# PCB.net
KiCad netlist of a schematic drawn in Altium Designer
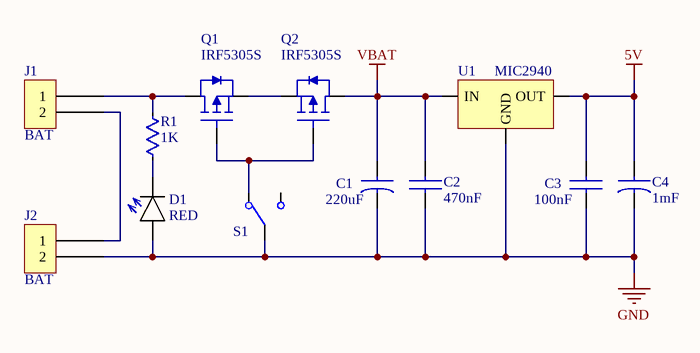
[diagram p0: PCB.SchDoc]

(export (version "E")
  (design (tool "Eeschema 10.0.6"))
  (components
    (comp (ref "C1")
      (value "220uF")
      (footprint "CAP-ELEC-5x11x2mm")
      (fields (field (name "Comment") "CAP-ELEC"))
      (libsource (lib "AltiumLibrary") (part "CAP-ELEC"))
    )
    (comp (ref "C2")
      (value "470nF")
      (footprint "C1206")
      (fields (field (name "Comment") "CAP-CER"))
      (libsource (lib "AltiumLibrary") (part "CAP-CER"))
    )
    (comp (ref "C3")
      (value "100nF")
      (footprint "C1206")
      (fields (field (name "Comment") "CAP-CER"))
      (libsource (lib "AltiumLibrary") (part "CAP-CER"))
    )
    (comp (ref "C4")
      (value "1mF")
      (footprint "CAP-ELEC-5x11x2mm")
      (fields (field (name "Comment") "CAP-ELEC"))
      (libsource (lib "AltiumLibrary") (part "CAP-ELEC"))
    )
    (comp (ref "D1") (value "RED") (footprint "LED-3MM-RED") (libsource (lib "AltiumLibrary") (part "LED")))
    (comp (ref "J1")
      (value "BAT")
      (footprint "HEADER 1x2")
      (libsource (lib "AltiumLibrary") (part "Header 1x2"))
    )
    (comp (ref "J2")
      (value "BAT")
      (footprint "HEADER 1x2")
      (libsource (lib "AltiumLibrary") (part "Header 1x2"))
    )
    (comp (ref "Q1")
      (value "IRF5305S")
      (footprint "TO-263")
      (libsource (lib "AltiumLibrary") (part "P-MOSFET"))
    )
    (comp (ref "Q2")
      (value "IRF5305S")
      (footprint "TO-263")
      (libsource (lib "AltiumLibrary") (part "P-MOSFET"))
    )
    (comp (ref "R1")
      (value "1K")
      (footprint "R1206")
      (fields (field (name "Comment") "RES"))
      (libsource (lib "AltiumLibrary") (part "RES"))
    )
    (comp (ref "S1")
      (value "SLIDE-SWITCH")
      (footprint "SWITCH")
      (libsource (lib "AltiumLibrary") (part "SLIDE-SWITCH"))
    )
    (comp (ref "U1") (value "MIC2940") (footprint "TO-263") (libsource (lib "AltiumLibrary") (part "LM2940")))
  )
  (nets
    (net (code "1") (name "5V") (class "Default")
      (node (ref "C3") (pin "2") (pintype "passive"))
      (node (ref "C4") (pin "1") (pintype "passive"))
      (node (ref "U1") (pin "3") (pinfunction "OUT_3") (pintype "power_in"))
    )
    (net (code "2") (name "GND") (class "Default")
      (node (ref "C1") (pin "2") (pintype "passive"))
      (node (ref "C2") (pin "1") (pintype "passive"))
      (node (ref "C3") (pin "1") (pintype "passive"))
      (node (ref "C4") (pin "2") (pintype "passive"))
      (node (ref "D1") (pin "A") (pintype "passive"))
      (node (ref "J2") (pin "2") (pinfunction "2_2") (pintype "passive"))
      (node (ref "S1") (pin "2") (pintype "power_in"))
      (node (ref "U1") (pin "2") (pinfunction "GND_2") (pintype "power_in"))
    )
    (net (code "3") (name "Net-(D1-PadK)") (class "Default")
      (node (ref "D1") (pin "K") (pintype "passive"))
      (node (ref "R1") (pin "1") (pintype "passive"))
    )
    (net (code "4") (name "Net-(J1-Pad1)") (class "Default")
      (node (ref "J1") (pin "1") (pinfunction "1_1") (pintype "passive"))
      (node (ref "Q1") (pin "D") (pintype "passive"))
      (node (ref "R1") (pin "2") (pintype "passive"))
    )
    (net (code "5") (name "Net-(J1-Pad2)") (class "Default")
      (node (ref "J1") (pin "2") (pinfunction "2_2") (pintype "passive"))
      (node (ref "J2") (pin "1") (pinfunction "1_1") (pintype "passive"))
    )
    (net (code "6") (name "Net-(Q1-PadG)") (class "Default")
      (node (ref "Q1") (pin "G") (pintype "passive"))
      (node (ref "Q2") (pin "G") (pintype "passive"))
      (node (ref "S1") (pin "1") (pintype "power_in"))
    )
    (net (code "7") (name "Net-(Q1-PadS)") (class "Default")
      (node (ref "Q1") (pin "S") (pintype "passive"))
      (node (ref "Q2") (pin "S") (pintype "passive"))
    )
    (net (code "8") (name "VBAT") (class "Default")
      (node (ref "C1") (pin "1") (pintype "passive"))
      (node (ref "C2") (pin "2") (pintype "passive"))
      (node (ref "Q2") (pin "D") (pintype "passive"))
      (node (ref "U1") (pin "1") (pinfunction "IN_1") (pintype "power_in"))
    )
    (net (code "9") (name "unconnected-(S1-Pad3)") (class "Default")
      (node (ref "S1") (pin "3") (pintype "power_in"))
    )
  )
)
